# SCH_LED_drill_2025-12-23.net
KiCad netlist of a schematic drawn in EasyEDA
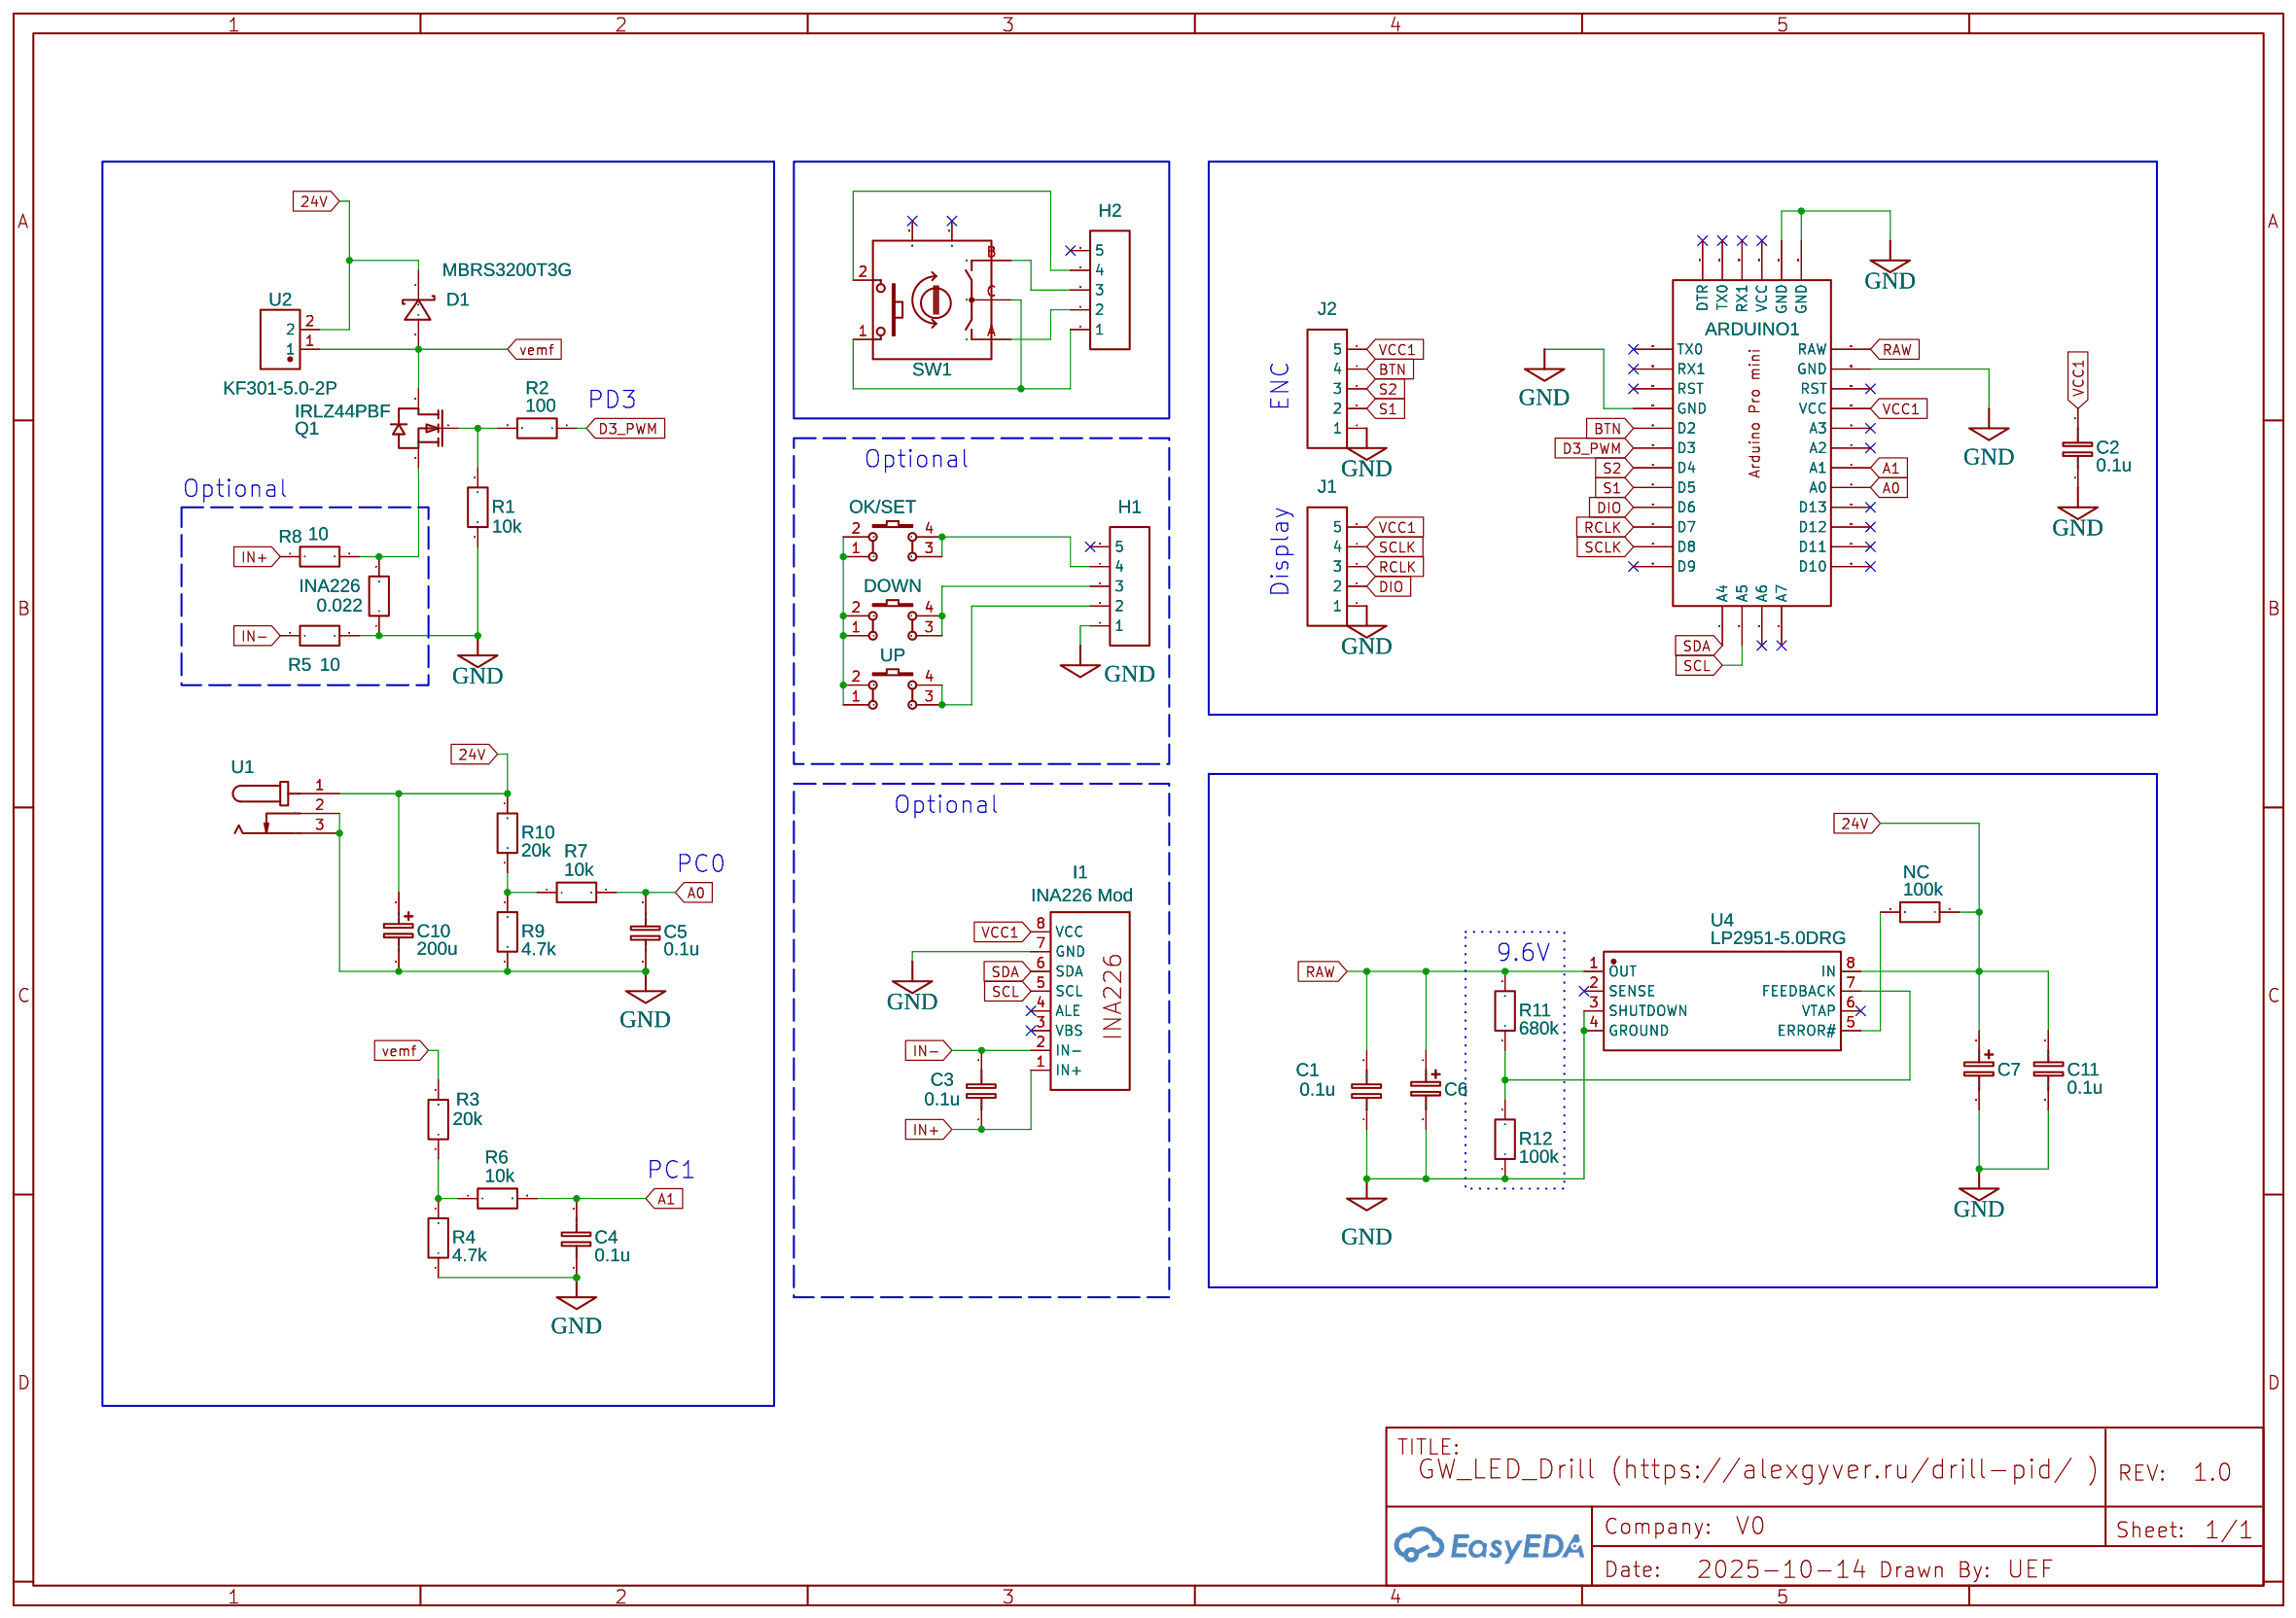
[diagram p0: Schematics]
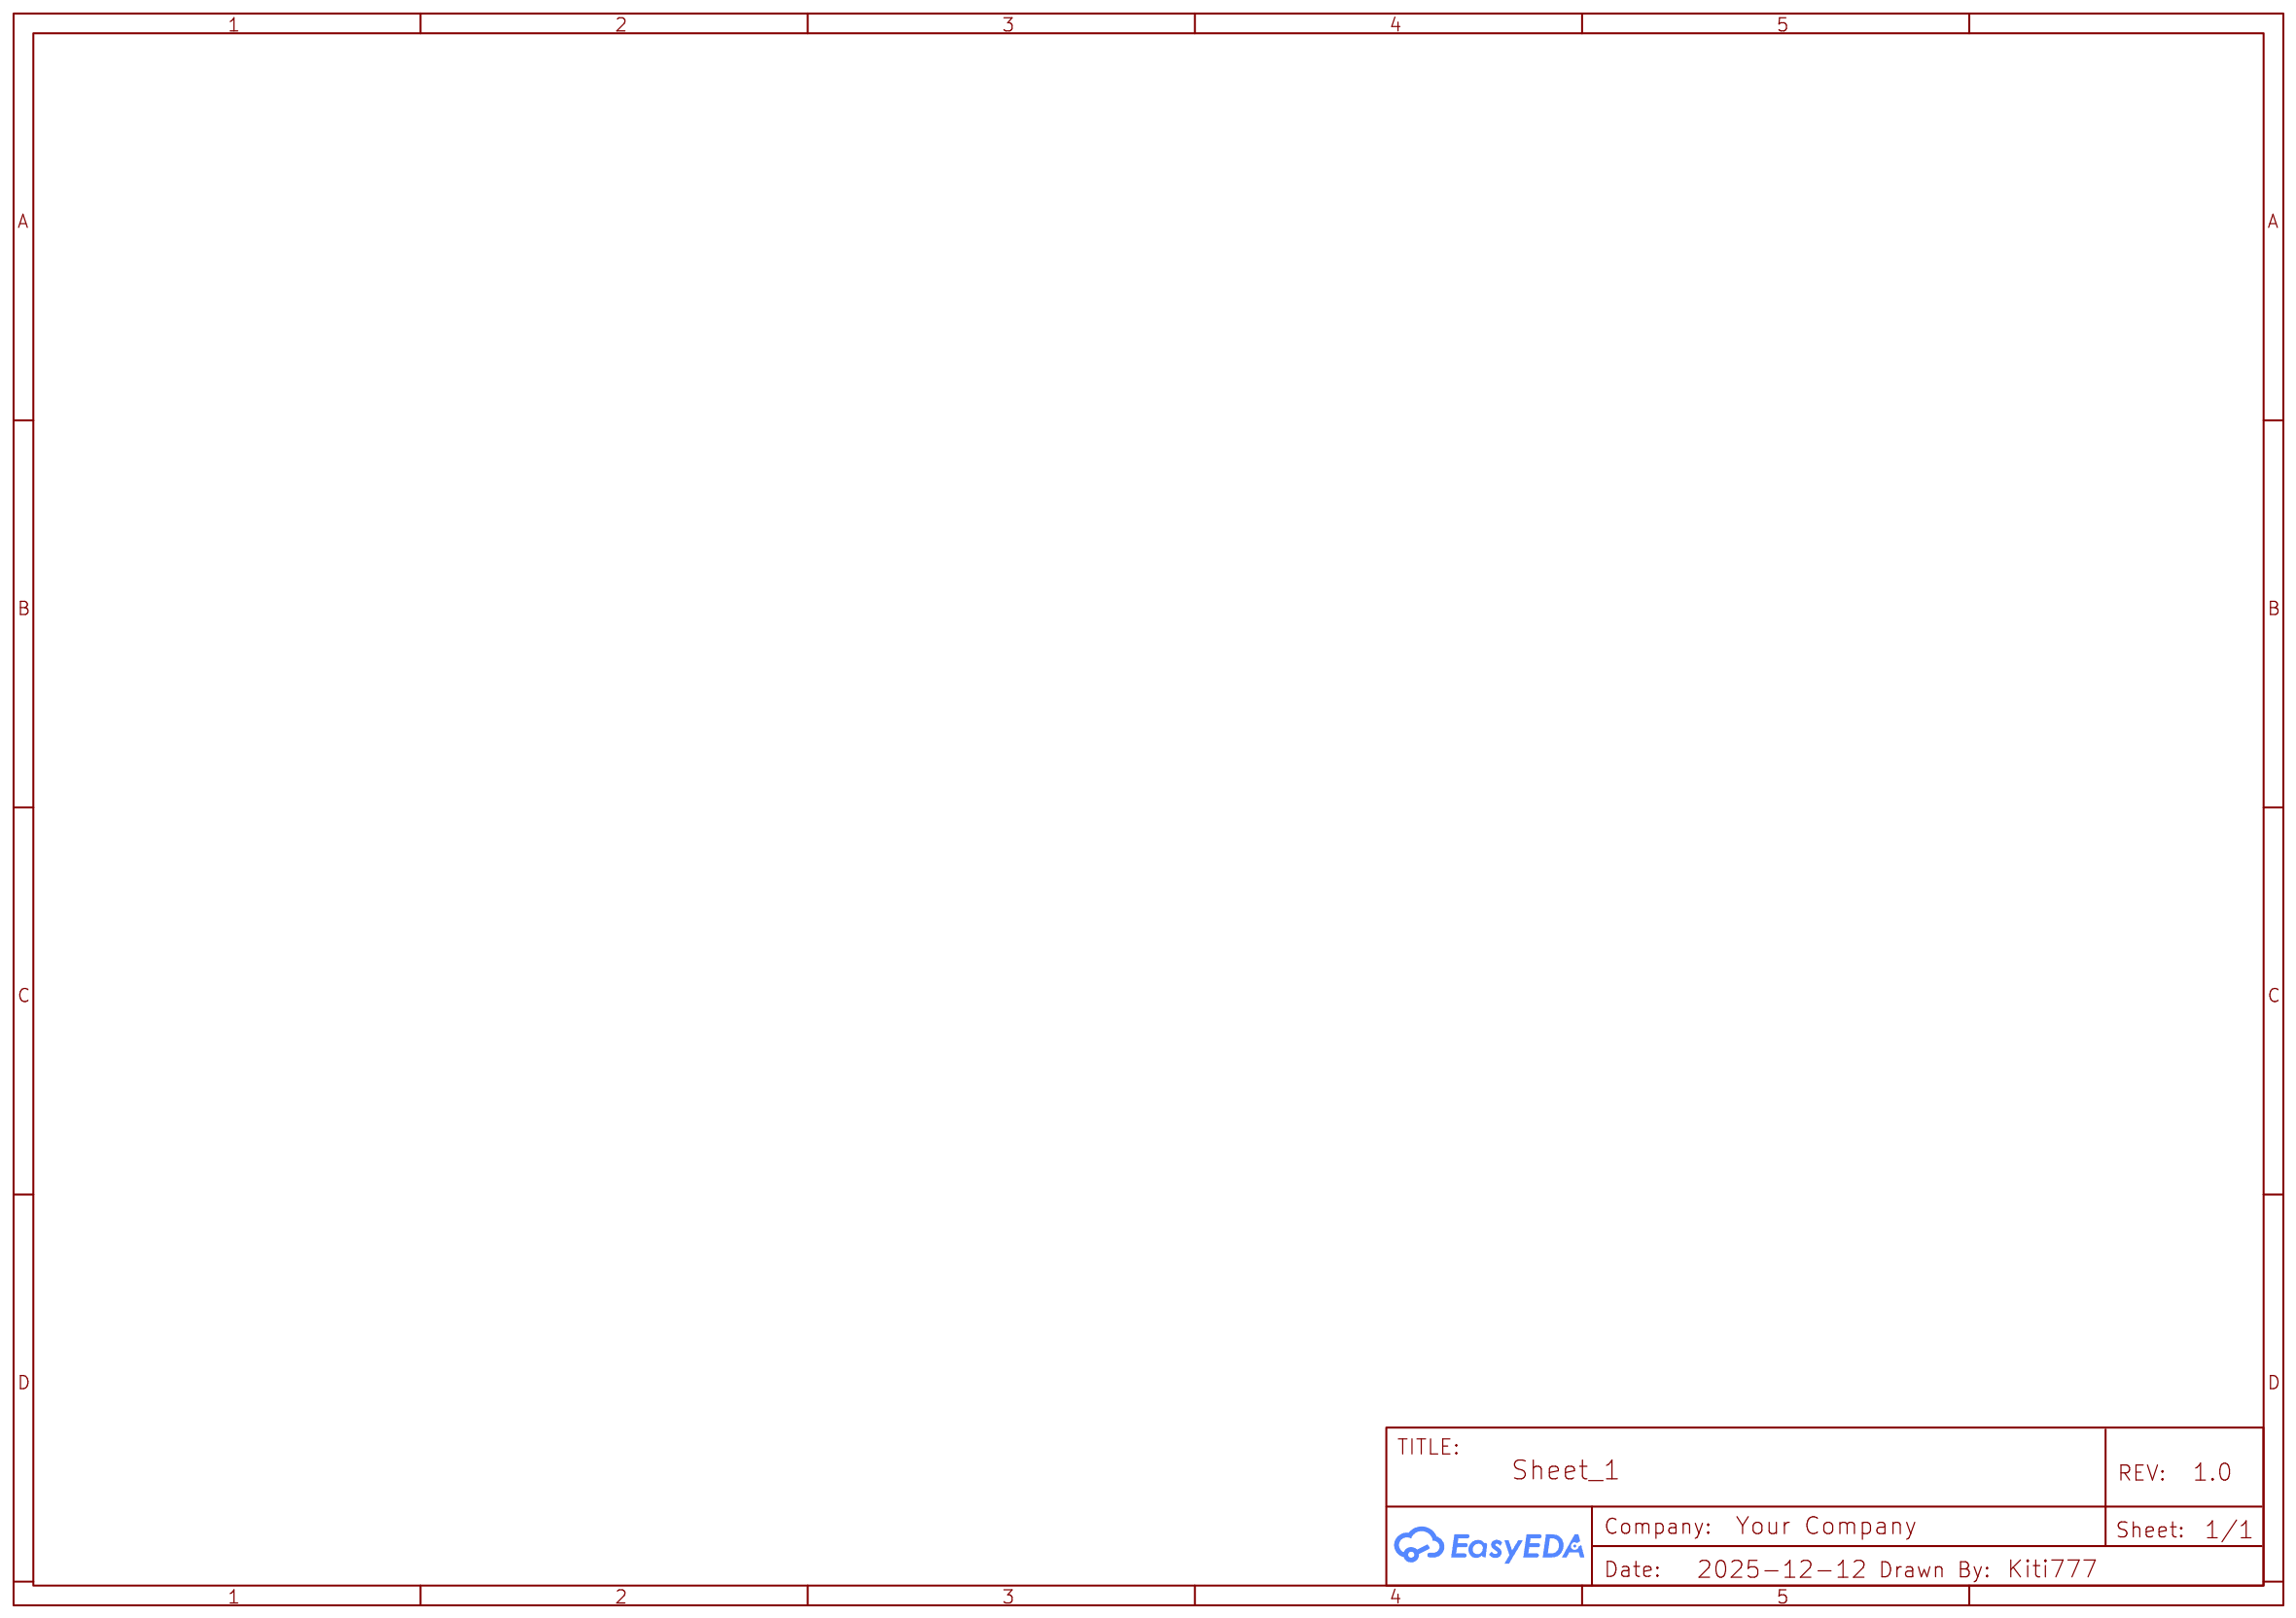
[diagram p1: INA226]

(export (version "E")
  (design (tool "Eeschema 10.0.6"))
  (components
    (comp (ref "ARDUINO1") (value "ARDUINO PRO MINI") (libsource (lib "") (part "ARDUINO PRO MINI")))
    (comp (ref "C1") (value "0.1u") (libsource (lib "") (part "C_1206_EU_2")))
    (comp (ref "C2") (value "0.1u") (libsource (lib "") (part "C_0805_EU_1")))
    (comp (ref "C3") (value "0.1u") (libsource (lib "") (part "C_0805_EU")))
    (comp (ref "C4") (value "0.1u") (libsource (lib "") (part "C_0805_EU")))
    (comp (ref "C5") (value "0.1u") (libsource (lib "") (part "C_1206_EU")))
    (comp (ref "C6")
      (value "TANTALUM SMT CAPACITOR 330UF C")
      (fields (field (name "Manufacturer Part") "Tantalum SMT Capacitor 330uF C"))
      (libsource (lib "") (part "TANTALUM SMT CAPACITOR 330UF C"))
    )
    (comp (ref "C7")
      (value "TANTALUM SMT CAPACITOR 330UF C")
      (fields (field (name "Manufacturer Part") "Tantalum SMT Capacitor 330uF C"))
      (libsource (lib "") (part "TANTALUM SMT CAPACITOR 330UF C"))
    )
    (comp (ref "C10") (value "200u") (libsource (lib "") (part "CE_SMD_D8.0×H10.5_EU")))
    (comp (ref "C11") (value "0.1u") (libsource (lib "") (part "C_1206_EU_1")))
    (comp (ref "D1")
      (value "MBRS3200T3G")
      (fields (field (name "Manufacturer") "onsemi(安森美)"))
      (libsource (lib "") (part "MBRS3200T3G"))
    )
    (comp (ref "DOWN")
      (value "K4-6×6_TH")
      (fields (field (name "Manufacturer Part") "K2-1102DP-E4SW-04") (field (name "Manufacturer") "韩国韩荣"))
      (libsource (lib "") (part "K4-6×6_TH"))
    )
    (comp (ref "H1") (value "HDR-F-2.54_1x5") (libsource (lib "") (part "HDR-F-2.54_1x5")))
    (comp (ref "H2") (value "HDR-F-2.54_1x5") (libsource (lib "") (part "HDR-F-2.54_1x5")))
    (comp (ref "I1") (value "INA226 Mod") (libsource (lib "") (part "INA226_1 Modulo")))
    (comp (ref "INA226") (value "0.022") (libsource (lib "") (part "R_2010_EU")))
    (comp (ref "J1") (value "HDR-M-2.54_1x5") (libsource (lib "") (part "HDR-M-2.54_1x5")))
    (comp (ref "J2") (value "HDR-M-2.54_1x5") (libsource (lib "") (part "HDR-M-2.54_1x5")))
    (comp (ref "NC") (value "100k") (libsource (lib "") (part "R_0805_EU_2")))
    (comp (ref "OK/SET")
      (value "K4-6×6_TH")
      (fields (field (name "Manufacturer Part") "K2-1102DP-E4SW-04") (field (name "Manufacturer") "韩国韩荣"))
      (libsource (lib "") (part "K4-6×6_TH_1"))
    )
    (comp (ref "Q1")
      (value "IRLZ44PBF")
      (fields (field (name "Manufacturer Part") "IRLZ44PBF-VB") (field (name "Manufacturer") "VBsemi(微碧半导体)"))
      (libsource (lib "") (part "IRLZ44PBF"))
    )
    (comp (ref "R1") (value "10k") (libsource (lib "") (part "R_1206_EU")))
    (comp (ref "R2") (value "100") (libsource (lib "") (part "R_1206_EU_1")))
    (comp (ref "R3") (value "20k") (libsource (lib "") (part "R_1206_EU")))
    (comp (ref "R4") (value "4.7k") (libsource (lib "") (part "R_1206_EU")))
    (comp (ref "R5") (value "10") (libsource (lib "") (part "R_0805_EU_1")))
    (comp (ref "R6") (value "10k") (libsource (lib "") (part "R_1206_EU_2")))
    (comp (ref "R7") (value "10k") (libsource (lib "") (part "R_1206_EU_2")))
    (comp (ref "R8") (value "10") (libsource (lib "") (part "R_0805_EU_1")))
    (comp (ref "R9") (value "4.7k") (libsource (lib "") (part "R_1206_EU")))
    (comp (ref "R10") (value "20k") (libsource (lib "") (part "R_1206_EU")))
    (comp (ref "R11") (value "680k") (libsource (lib "") (part "R_0805_EU")))
    (comp (ref "R12") (value "100k") (libsource (lib "") (part "R_0805_EU")))
    (comp (ref "SW1")
      (value "PEC11R-4015F-S0024")
      (fields (field (name "Manufacturer") "BOURNS"))
      (libsource (lib "") (part "PEC11R-4015F-S0024"))
    )
    (comp (ref "U1")
      (value "ZX-DC-WC26.4")
      (fields (field (name "Manufacturer") "Megastar(兆星)"))
      (libsource (lib "") (part "ZX-DC-WC26.4"))
    )
    (comp (ref "U2")
      (value "KF301-5.0-2P")
      (fields (field (name "Manufacturer") "KEFA(科发)"))
      (libsource (lib "") (part "KF301-5.0-2P"))
    )
    (comp (ref "U4")
      (value "LP2951-5.0DRG")
      (fields (field (name "Manufacturer") "HGC(深圳汉芯)"))
      (libsource (lib "") (part "LP2951-5.0DRG"))
    )
    (comp (ref "UP")
      (value "K4-6×6_TH")
      (fields (field (name "Manufacturer Part") "K2-1102DP-E4SW-04") (field (name "Manufacturer") "韩国韩荣"))
      (libsource (lib "") (part "K4-6×6_TH_2"))
    )
  )
  (nets
    (net (code "1") (name "24V") (class "Default")
      (node (ref "C10") (pin "1") (pinfunction "1_1") (pintype "unspecified"))
      (node (ref "C11") (pin "1") (pinfunction "1_1") (pintype "unspecified"))
      (node (ref "C7") (pin "1") (pinfunction "1_1") (pintype "unspecified"))
      (node (ref "D1") (pin "1") (pinfunction "C_1") (pintype "unspecified"))
      (node (ref "NC") (pin "1") (pinfunction "1_1") (pintype "unspecified"))
      (node (ref "R10") (pin "2") (pinfunction "2_2") (pintype "unspecified"))
      (node (ref "U1") (pin "1") (pinfunction "1_1") (pintype "unspecified"))
      (node (ref "U2") (pin "2") (pinfunction "2_2") (pintype "unspecified"))
      (node (ref "U4") (pin "8") (pinfunction "IN_8") (pintype "unspecified"))
    )
    (net (code "2") (name "A0") (class "Default")
      (node (ref "ARDUINO1") (pin "A0") (pinfunction "A0_A0") (pintype "bidirectional"))
      (node (ref "C5") (pin "2") (pinfunction "2_2") (pintype "unspecified"))
      (node (ref "R7") (pin "2") (pinfunction "2_2") (pintype "unspecified"))
    )
    (net (code "3") (name "A1") (class "Default")
      (node (ref "ARDUINO1") (pin "A1") (pinfunction "A1_A1") (pintype "bidirectional"))
      (node (ref "C4") (pin "2") (pinfunction "2_2") (pintype "unspecified"))
      (node (ref "R6") (pin "2") (pinfunction "2_2") (pintype "unspecified"))
    )
    (net (code "4") (name "BTN") (class "Default")
      (node (ref "ARDUINO1") (pin "D2") (pinfunction "D2_D2") (pintype "bidirectional"))
      (node (ref "J2") (pin "4") (pinfunction "4_4") (pintype "unspecified"))
    )
    (net (code "5") (name "D3_PWM") (class "Default")
      (node (ref "ARDUINO1") (pin "D3") (pinfunction "D3_D3") (pintype "bidirectional"))
      (node (ref "R2") (pin "1") (pinfunction "1_1") (pintype "unspecified"))
    )
    (net (code "6") (name "DIO") (class "Default")
      (node (ref "ARDUINO1") (pin "D6") (pinfunction "D6_D6") (pintype "bidirectional"))
      (node (ref "J1") (pin "2") (pinfunction "2_2") (pintype "unspecified"))
    )
    (net (code "7") (name "GND") (class "Default")
      (node (ref "ARDUINO1") (pin "GND@0") (pinfunction "GND_GND@0") (pintype "bidirectional"))
      (node (ref "ARDUINO1") (pin "GND@1") (pinfunction "GND_GND@1") (pintype "bidirectional"))
      (node (ref "ARDUINO1") (pin "GND@2") (pinfunction "GND_GND@2") (pintype "bidirectional"))
      (node (ref "ARDUINO1") (pin "GND@3") (pinfunction "GND_GND@3") (pintype "bidirectional"))
      (node (ref "C1") (pin "1") (pinfunction "1_1") (pintype "unspecified"))
      (node (ref "C10") (pin "2") (pinfunction "2_2") (pintype "unspecified"))
      (node (ref "C11") (pin "2") (pinfunction "2_2") (pintype "unspecified"))
      (node (ref "C2") (pin "1") (pinfunction "1_1") (pintype "unspecified"))
      (node (ref "C4") (pin "1") (pinfunction "1_1") (pintype "unspecified"))
      (node (ref "C5") (pin "1") (pinfunction "1_1") (pintype "unspecified"))
      (node (ref "C6") (pin "2") (pinfunction "2_2") (pintype "unspecified"))
      (node (ref "C7") (pin "2") (pinfunction "2_2") (pintype "unspecified"))
      (node (ref "H1") (pin "1") (pinfunction "1_1") (pintype "unspecified"))
      (node (ref "I1") (pin "7") (pinfunction "GND_7") (pintype "unspecified"))
      (node (ref "INA226") (pin "1") (pinfunction "1_1") (pintype "unspecified"))
      (node (ref "J1") (pin "1") (pinfunction "1_1") (pintype "unspecified"))
      (node (ref "J2") (pin "1") (pinfunction "1_1") (pintype "unspecified"))
      (node (ref "R1") (pin "1") (pinfunction "1_1") (pintype "unspecified"))
      (node (ref "R12") (pin "1") (pinfunction "1_1") (pintype "unspecified"))
      (node (ref "R4") (pin "1") (pinfunction "1_1") (pintype "unspecified"))
      (node (ref "R5") (pin "2") (pinfunction "2_2") (pintype "unspecified"))
      (node (ref "R9") (pin "1") (pinfunction "1_1") (pintype "unspecified"))
      (node (ref "U1") (pin "2") (pinfunction "2_2") (pintype "unspecified"))
      (node (ref "U1") (pin "3") (pinfunction "3_3") (pintype "unspecified"))
      (node (ref "U4") (pin "3") (pinfunction "SHUTDOWN_3") (pintype "unspecified"))
      (node (ref "U4") (pin "4") (pinfunction "GROUND_4") (pintype "unspecified"))
    )
    (net (code "8") (name "IN+") (class "Default")
      (node (ref "C3") (pin "1") (pinfunction "1_1") (pintype "unspecified"))
      (node (ref "I1") (pin "1") (pinfunction "IN+_1") (pintype "unspecified"))
      (node (ref "R8") (pin "1") (pinfunction "1_1") (pintype "unspecified"))
    )
    (net (code "9") (name "IN-") (class "Default")
      (node (ref "C3") (pin "2") (pinfunction "2_2") (pintype "unspecified"))
      (node (ref "I1") (pin "2") (pinfunction "IN-_2") (pintype "unspecified"))
      (node (ref "R5") (pin "1") (pinfunction "1_1") (pintype "unspecified"))
    )
    (net (code "10") (name "Net-(DOWN-Pad1)") (class "Default")
      (node (ref "DOWN") (pin "1") (pinfunction "1_1") (pintype "unspecified"))
      (node (ref "DOWN") (pin "2") (pinfunction "2_2") (pintype "unspecified"))
      (node (ref "OK/SET") (pin "1") (pinfunction "1_1") (pintype "unspecified"))
      (node (ref "OK/SET") (pin "2") (pinfunction "2_2") (pintype "unspecified"))
      (node (ref "UP") (pin "1") (pinfunction "1_1") (pintype "unspecified"))
      (node (ref "UP") (pin "2") (pinfunction "2_2") (pintype "unspecified"))
    )
    (net (code "11") (name "Net-(DOWN-Pad3)") (class "Default")
      (node (ref "DOWN") (pin "3") (pinfunction "3_3") (pintype "unspecified"))
      (node (ref "DOWN") (pin "4") (pinfunction "4_4") (pintype "unspecified"))
      (node (ref "H1") (pin "3") (pinfunction "3_3") (pintype "unspecified"))
    )
    (net (code "12") (name "Net-(H1-Pad2)") (class "Default")
      (node (ref "H1") (pin "2") (pinfunction "2_2") (pintype "unspecified"))
      (node (ref "UP") (pin "3") (pinfunction "3_3") (pintype "unspecified"))
      (node (ref "UP") (pin "4") (pinfunction "4_4") (pintype "unspecified"))
    )
    (net (code "13") (name "Net-(H1-Pad4)") (class "Default")
      (node (ref "H1") (pin "4") (pinfunction "4_4") (pintype "unspecified"))
      (node (ref "OK/SET") (pin "3") (pinfunction "3_3") (pintype "unspecified"))
      (node (ref "OK/SET") (pin "4") (pinfunction "4_4") (pintype "unspecified"))
    )
    (net (code "14") (name "Net-(H2-Pad1)") (class "Default")
      (node (ref "H2") (pin "1") (pinfunction "1_1") (pintype "unspecified"))
      (node (ref "SW1") (pin "1") (pinfunction "1_1") (pintype "unspecified"))
      (node (ref "SW1") (pin "C") (pinfunction "C_C") (pintype "unspecified"))
    )
    (net (code "15") (name "Net-(H2-Pad2)") (class "Default")
      (node (ref "H2") (pin "2") (pinfunction "2_2") (pintype "unspecified"))
      (node (ref "SW1") (pin "A") (pinfunction "A_A") (pintype "unspecified"))
    )
    (net (code "16") (name "Net-(H2-Pad3)") (class "Default")
      (node (ref "H2") (pin "3") (pinfunction "3_3") (pintype "unspecified"))
      (node (ref "SW1") (pin "B") (pinfunction "B_B") (pintype "unspecified"))
    )
    (net (code "17") (name "Net-(H2-Pad4)") (class "Default")
      (node (ref "H2") (pin "4") (pinfunction "4_4") (pintype "unspecified"))
      (node (ref "SW1") (pin "2") (pinfunction "2_2") (pintype "unspecified"))
    )
    (net (code "18") (name "Net-(Q1-G)") (class "Default")
      (node (ref "Q1") (pin "1") (pinfunction "G_1") (pintype "unspecified"))
      (node (ref "R1") (pin "2") (pinfunction "2_2") (pintype "unspecified"))
      (node (ref "R2") (pin "2") (pinfunction "2_2") (pintype "unspecified"))
    )
    (net (code "19") (name "Net-(Q1-S)") (class "Default")
      (node (ref "INA226") (pin "2") (pinfunction "2_2") (pintype "unspecified"))
      (node (ref "Q1") (pin "3") (pinfunction "S_3") (pintype "unspecified"))
      (node (ref "R8") (pin "2") (pinfunction "2_2") (pintype "unspecified"))
    )
    (net (code "20") (name "Net-(R3-Pad1)") (class "Default")
      (node (ref "R3") (pin "1") (pinfunction "1_1") (pintype "unspecified"))
      (node (ref "R4") (pin "2") (pinfunction "2_2") (pintype "unspecified"))
      (node (ref "R6") (pin "1") (pinfunction "1_1") (pintype "unspecified"))
    )
    (net (code "21") (name "Net-(R10-Pad1)") (class "Default")
      (node (ref "R10") (pin "1") (pinfunction "1_1") (pintype "unspecified"))
      (node (ref "R7") (pin "1") (pinfunction "1_1") (pintype "unspecified"))
      (node (ref "R9") (pin "2") (pinfunction "2_2") (pintype "unspecified"))
    )
    (net (code "22") (name "Net-(U4-ERROR#)") (class "Default")
      (node (ref "NC") (pin "2") (pinfunction "2_2") (pintype "unspecified"))
      (node (ref "U4") (pin "5") (pinfunction "ERROR#_5") (pintype "unspecified"))
    )
    (net (code "23") (name "Net-(U4-FEEDBACK)") (class "Default")
      (node (ref "R11") (pin "1") (pinfunction "1_1") (pintype "unspecified"))
      (node (ref "R12") (pin "2") (pinfunction "2_2") (pintype "unspecified"))
      (node (ref "U4") (pin "7") (pinfunction "FEEDBACK_7") (pintype "unspecified"))
    )
    (net (code "24") (name "RAW") (class "Default")
      (node (ref "ARDUINO1") (pin "RAW") (pinfunction "RAW_RAW") (pintype "bidirectional"))
      (node (ref "C1") (pin "2") (pinfunction "2_2") (pintype "unspecified"))
      (node (ref "C6") (pin "1") (pinfunction "1_1") (pintype "unspecified"))
      (node (ref "R11") (pin "2") (pinfunction "2_2") (pintype "unspecified"))
      (node (ref "U4") (pin "1") (pinfunction "OUT_1") (pintype "unspecified"))
    )
    (net (code "25") (name "RCLK") (class "Default")
      (node (ref "ARDUINO1") (pin "D7") (pinfunction "D7_D7") (pintype "bidirectional"))
      (node (ref "J1") (pin "3") (pinfunction "3_3") (pintype "unspecified"))
    )
    (net (code "26") (name "S1") (class "Default")
      (node (ref "ARDUINO1") (pin "D5") (pinfunction "D5_D5") (pintype "bidirectional"))
      (node (ref "J2") (pin "2") (pinfunction "2_2") (pintype "unspecified"))
    )
    (net (code "27") (name "S2") (class "Default")
      (node (ref "ARDUINO1") (pin "D4") (pinfunction "D4_D4") (pintype "bidirectional"))
      (node (ref "J2") (pin "3") (pinfunction "3_3") (pintype "unspecified"))
    )
    (net (code "28") (name "SCL") (class "Default")
      (node (ref "ARDUINO1") (pin "A5") (pinfunction "A5_A5") (pintype "bidirectional"))
      (node (ref "I1") (pin "5") (pinfunction "SCL_5") (pintype "unspecified"))
    )
    (net (code "29") (name "SCLK") (class "Default")
      (node (ref "ARDUINO1") (pin "D8") (pinfunction "D8_D8") (pintype "bidirectional"))
      (node (ref "J1") (pin "4") (pinfunction "4_4") (pintype "unspecified"))
    )
    (net (code "30") (name "SDA") (class "Default")
      (node (ref "ARDUINO1") (pin "A4") (pinfunction "A4_A4") (pintype "bidirectional"))
      (node (ref "I1") (pin "6") (pinfunction "SDA_6") (pintype "unspecified"))
    )
    (net (code "31") (name "VCC1") (class "Default")
      (node (ref "ARDUINO1") (pin "VCC@1") (pinfunction "VCC_VCC@1") (pintype "bidirectional"))
      (node (ref "C2") (pin "2") (pinfunction "2_2") (pintype "unspecified"))
      (node (ref "I1") (pin "8") (pinfunction "VCC_8") (pintype "unspecified"))
      (node (ref "J1") (pin "5") (pinfunction "5_5") (pintype "unspecified"))
      (node (ref "J2") (pin "5") (pinfunction "5_5") (pintype "unspecified"))
    )
    (net (code "32") (name "unconnected-(ARDUINO1-PadA2)") (class "Default")
      (node (ref "ARDUINO1") (pin "A2") (pinfunction "A2_A2") (pintype "bidirectional+no_connect"))
    )
    (net (code "33") (name "unconnected-(ARDUINO1-PadA3)") (class "Default")
      (node (ref "ARDUINO1") (pin "A3") (pinfunction "A3_A3") (pintype "bidirectional+no_connect"))
    )
    (net (code "34") (name "unconnected-(ARDUINO1-PadA6)") (class "Default")
      (node (ref "ARDUINO1") (pin "A6") (pinfunction "A6_A6") (pintype "bidirectional+no_connect"))
    )
    (net (code "35") (name "unconnected-(ARDUINO1-PadA7)") (class "Default")
      (node (ref "ARDUINO1") (pin "A7") (pinfunction "A7_A7") (pintype "bidirectional+no_connect"))
    )
    (net (code "36") (name "unconnected-(ARDUINO1-PadD9)") (class "Default")
      (node (ref "ARDUINO1") (pin "D9") (pinfunction "D9_D9") (pintype "bidirectional+no_connect"))
    )
    (net (code "37") (name "unconnected-(ARDUINO1-PadD10)") (class "Default")
      (node (ref "ARDUINO1") (pin "D10") (pinfunction "D10_D10") (pintype "bidirectional+no_connect"))
    )
    (net (code "38") (name "unconnected-(ARDUINO1-PadD11)") (class "Default")
      (node (ref "ARDUINO1") (pin "D11") (pinfunction "D11_D11") (pintype "bidirectional+no_connect"))
    )
    (net (code "39") (name "unconnected-(ARDUINO1-PadD12)") (class "Default")
      (node (ref "ARDUINO1") (pin "D12") (pinfunction "D12_D12") (pintype "bidirectional+no_connect"))
    )
    (net (code "40") (name "unconnected-(ARDUINO1-PadD13)") (class "Default")
      (node (ref "ARDUINO1") (pin "D13") (pinfunction "D13_D13") (pintype "bidirectional+no_connect"))
    )
    (net (code "41") (name "unconnected-(ARDUINO1-PadDTR)") (class "Default")
      (node (ref "ARDUINO1") (pin "DTR") (pinfunction "DTR_DTR") (pintype "bidirectional+no_connect"))
    )
    (net (code "42") (name "unconnected-(ARDUINO1-RST-PadRST@0)") (class "Default")
      (node (ref "ARDUINO1") (pin "RST@0") (pinfunction "RST_RST@0") (pintype "bidirectional+no_connect"))
    )
    (net (code "43") (name "unconnected-(ARDUINO1-RST-PadRST@1)") (class "Default")
      (node (ref "ARDUINO1") (pin "RST@1") (pinfunction "RST_RST@1") (pintype "bidirectional+no_connect"))
    )
    (net (code "44") (name "unconnected-(ARDUINO1-RX1-PadRX1@0)") (class "Default")
      (node (ref "ARDUINO1") (pin "RX1@0") (pinfunction "RX1_RX1@0") (pintype "bidirectional+no_connect"))
    )
    (net (code "45") (name "unconnected-(ARDUINO1-RX1-PadRX1@1)") (class "Default")
      (node (ref "ARDUINO1") (pin "RX1@1") (pinfunction "RX1_RX1@1") (pintype "bidirectional+no_connect"))
    )
    (net (code "46") (name "unconnected-(ARDUINO1-TX0-PadTX0@0)") (class "Default")
      (node (ref "ARDUINO1") (pin "TX0@0") (pinfunction "TX0_TX0@0") (pintype "bidirectional+no_connect"))
    )
    (net (code "47") (name "unconnected-(ARDUINO1-TX0-PadTX0@1)") (class "Default")
      (node (ref "ARDUINO1") (pin "TX0@1") (pinfunction "TX0_TX0@1") (pintype "bidirectional+no_connect"))
    )
    (net (code "48") (name "unconnected-(ARDUINO1-VCC-PadVCC@0)") (class "Default")
      (node (ref "ARDUINO1") (pin "VCC@0") (pinfunction "VCC_VCC@0") (pintype "bidirectional+no_connect"))
    )
    (net (code "49") (name "unconnected-(H1-Pad5)") (class "Default")
      (node (ref "H1") (pin "5") (pinfunction "5_5") (pintype "unspecified+no_connect"))
    )
    (net (code "50") (name "unconnected-(H2-Pad5)") (class "Default")
      (node (ref "H2") (pin "5") (pinfunction "5_5") (pintype "unspecified+no_connect"))
    )
    (net (code "51") (name "unconnected-(I1-ALE-Pad4)") (class "Default")
      (node (ref "I1") (pin "4") (pinfunction "ALE_4") (pintype "unspecified+no_connect"))
    )
    (net (code "52") (name "unconnected-(I1-VBS-Pad3)") (class "Default")
      (node (ref "I1") (pin "3") (pinfunction "VBS_3") (pintype "unspecified+no_connect"))
    )
    (net (code "53") (name "unconnected-(SW1-PadMT1)") (class "Default")
      (node (ref "SW1") (pin "MT1") (pinfunction "MT1_MT1") (pintype "unspecified+no_connect"))
    )
    (net (code "54") (name "unconnected-(SW1-PadMT2)") (class "Default")
      (node (ref "SW1") (pin "MT2") (pinfunction "MT2_MT2") (pintype "unspecified+no_connect"))
    )
    (net (code "55") (name "unconnected-(U4-SENSE-Pad2)") (class "Default")
      (node (ref "U4") (pin "2") (pinfunction "SENSE_2") (pintype "unspecified+no_connect"))
    )
    (net (code "56") (name "unconnected-(U4-VTAP-Pad6)") (class "Default")
      (node (ref "U4") (pin "6") (pinfunction "VTAP_6") (pintype "unspecified+no_connect"))
    )
    (net (code "57") (name "vemf") (class "Default")
      (node (ref "D1") (pin "2") (pinfunction "A_2") (pintype "unspecified"))
      (node (ref "Q1") (pin "2") (pinfunction "D_2") (pintype "unspecified"))
      (node (ref "R3") (pin "2") (pinfunction "2_2") (pintype "unspecified"))
      (node (ref "U2") (pin "1") (pinfunction "1_1") (pintype "unspecified"))
    )
  )
)
